# power.net
KiCad netlist of a schematic drawn in Altium Designer
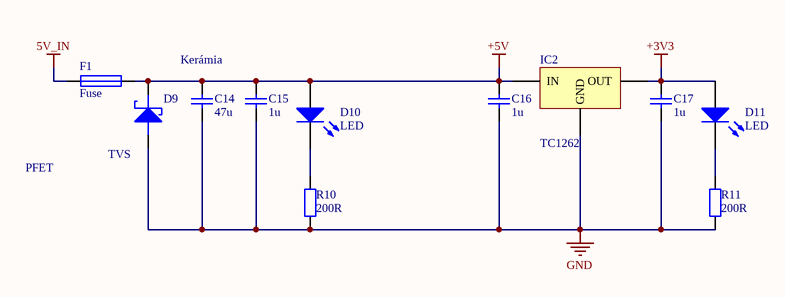
[diagram p0: power.SchDoc]

(export (version "E")
  (design (tool "Eeschema 10.0.6"))
  (components
    (comp (ref "C14")
      (value "47u")
      (footprint "FP_0805_CAP_085")
      (description "Capacitor")
      (libsource (lib "hallglib") (part "CAP"))
    )
    (comp (ref "C15")
      (value "1u")
      (footprint "FP_0805_CAP_085")
      (description "Capacitor")
      (libsource (lib "hallglib") (part "CAP"))
    )
    (comp (ref "C16")
      (value "1u")
      (footprint "FP_0805_CAP_085")
      (description "Capacitor")
      (libsource (lib "hallglib") (part "CAP"))
    )
    (comp (ref "C17")
      (value "1u")
      (footprint "FP_0805_CAP_085")
      (description "Capacitor")
      (libsource (lib "hallglib") (part "CAP"))
    )
    (comp (ref "D9")
      (value "TVS")
      (footprint "FP_SMB")
      (description "TVS diode")
      (libsource (lib "hallglib") (part "SCHOTTKY"))
    )
    (comp (ref "D10")
      (value "LED")
      (footprint "FP_0805_LED_GREEN")
      (description "Typical RED GaAs LED")
      (libsource (lib "hallglib") (part "LED"))
    )
    (comp (ref "D11")
      (value "LED")
      (footprint "FP_0805_LED_GREEN")
      (description "Typical RED GaAs LED")
      (libsource (lib "hallglib") (part "LED"))
    )
    (comp (ref "F1") (value "Fuse") (footprint "FP_MULTIFUSE") (libsource (lib "hallglib") (part "Fuse")))
    (comp (ref "IC2")
      (value "TC1262")
      (footprint "FP_SOT223")
      (description "Fixed LDO Voltage Regulator")
      (libsource (lib "mb") (part "TC1262"))
    )
    (comp (ref "R10")
      (value "200R")
      (footprint "FP_0805_RES")
      (description "Resistor")
      (libsource (lib "hallglib") (part "RES"))
    )
    (comp (ref "R11")
      (value "200R")
      (footprint "FP_0805_RES")
      (description "Resistor")
      (libsource (lib "hallglib") (part "RES"))
    )
  )
  (nets
    (net (code "1") (name "+3V3") (class "Default")
      (node (ref "C17") (pin "2") (pinfunction "2_2") (pintype "passive"))
      (node (ref "D11") (pin "1") (pinfunction "A_1") (pintype "passive"))
      (node (ref "IC2") (pin "3") (pinfunction "OUT_3") (pintype "passive"))
    )
    (net (code "2") (name "+5V") (class "Default")
      (node (ref "C14") (pin "2") (pinfunction "2_2") (pintype "passive"))
      (node (ref "C15") (pin "2") (pinfunction "2_2") (pintype "passive"))
      (node (ref "C16") (pin "2") (pinfunction "2_2") (pintype "passive"))
      (node (ref "D10") (pin "1") (pinfunction "A_1") (pintype "passive"))
      (node (ref "D9") (pin "1") (pinfunction "CATHODE_1") (pintype "passive"))
      (node (ref "F1") (pin "2") (pinfunction "2_2") (pintype "passive"))
      (node (ref "IC2") (pin "1") (pinfunction "IN_1") (pintype "passive"))
    )
    (net (code "3") (name "5V_IN") (class "Default")
      (node (ref "F1") (pin "1") (pinfunction "1_1") (pintype "passive"))
    )
    (net (code "4") (name "GND") (class "Default")
      (node (ref "C14") (pin "1") (pinfunction "1_1") (pintype "passive"))
      (node (ref "C15") (pin "1") (pinfunction "1_1") (pintype "passive"))
      (node (ref "C16") (pin "1") (pinfunction "1_1") (pintype "passive"))
      (node (ref "C17") (pin "1") (pinfunction "1_1") (pintype "passive"))
      (node (ref "D9") (pin "2") (pinfunction "ANODE_2") (pintype "passive"))
      (node (ref "IC2") (pin "2") (pinfunction "GND_2") (pintype "passive"))
      (node (ref "R10") (pin "1") (pinfunction "1_1") (pintype "passive"))
      (node (ref "R11") (pin "1") (pinfunction "1_1") (pintype "passive"))
    )
    (net (code "5") (name "Net-(D10-K)") (class "Default")
      (node (ref "D10") (pin "2") (pinfunction "K_2") (pintype "passive"))
      (node (ref "R10") (pin "2") (pinfunction "2_2") (pintype "passive"))
    )
    (net (code "6") (name "Net-(D11-K)") (class "Default")
      (node (ref "D11") (pin "2") (pinfunction "K_2") (pintype "passive"))
      (node (ref "R11") (pin "2") (pinfunction "2_2") (pintype "passive"))
    )
  )
)
